# Main.net
KiCad netlist of a schematic drawn in Altium Designer
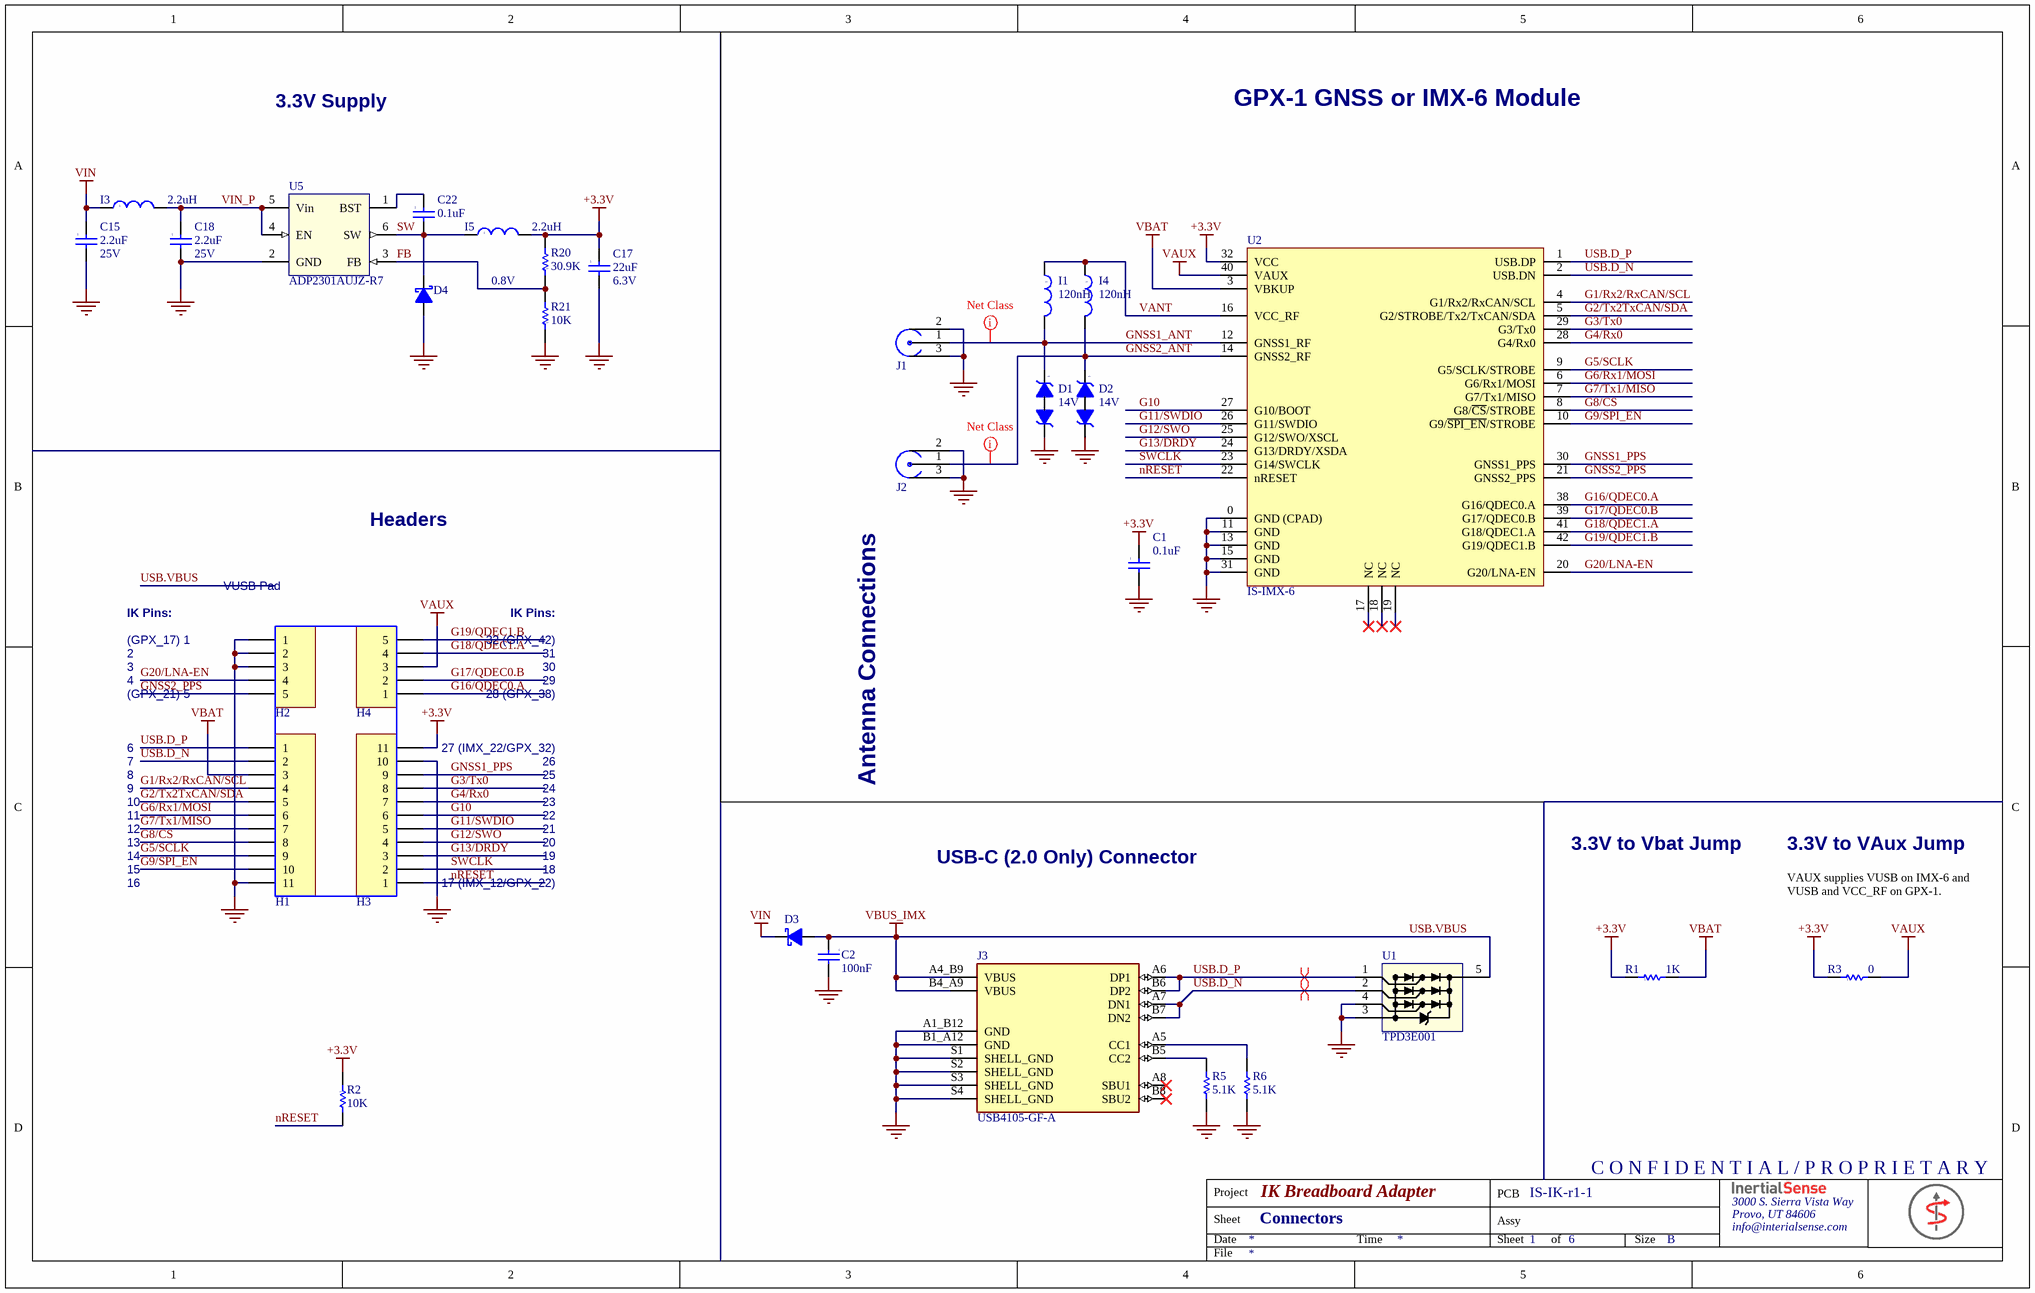
[diagram p0: Main.SchDoc]

(export (version "E")
  (design (tool "Eeschema 10.0.6"))
  (components
    (comp (ref "C1")
      (value "0.1uF")
      (footprint "0402")
      (description "CAP CER .10UF 50V X7R 10% 0402")
      (fields
        (field (name "MANUFACTURER") "TDK Corporation")
        (field (name "MANUFACTURER PART NUMBER") "C1005X7R1H104K")
        (field (name "PUBLISHER") "Altium Limited")
      )
      (libsource (lib "General") (part "Cap"))
    )
    (comp (ref "C2")
      (value "100nF")
      (footprint "0402")
      (description "CAP CER .10UF 50V X7R 10% 0402")
      (fields
        (field (name "MANUFACTURER") "TDK Corporation")
        (field (name "MANUFACTURER PART NUMBER") "C1005X7R1H104K")
        (field (name "PUBLISHER") "Altium Limited")
      )
      (libsource (lib "General") (part "Cap"))
    )
    (comp (ref "C15")
      (value "2.2uF")
      (footprint "0603")
      (description "CAP CER 2.2UF 25V X6S 0603")
      (fields
        (field (name "MANUFACTURER") "Murata")
        (field (name "MANUFACTURER PART NUMBER") "GRT188C81E225KE13D")
        (field (name "VOLTAGE RATING") "25V")
        (field (name "PUBLISHER") "Altium Limited")
      )
      (libsource (lib "General") (part "Cap"))
    )
    (comp (ref "C17")
      (value "22uF")
      (footprint "0603")
      (description "CAP CER 22UF 6.3V X6S 0603")
      (fields
        (field (name "MANUFACTURER") "Murata")
        (field (name "MANUFACTURER PART NUMBER") "GRM188C80J226ME15D")
        (field (name "VOLTAGE RATING") "6.3V")
        (field (name "PUBLISHER") "Altium Limited")
      )
      (libsource (lib "General") (part "Cap"))
    )
    (comp (ref "C18")
      (value "2.2uF")
      (footprint "0603")
      (description "CAP CER 2.2UF 25V X6S 0603")
      (fields
        (field (name "MANUFACTURER") "Murata")
        (field (name "MANUFACTURER PART NUMBER") "GRT188C81E225KE13D")
        (field (name "VOLTAGE RATING") "25V")
        (field (name "PUBLISHER") "Altium Limited")
      )
      (libsource (lib "General") (part "Cap"))
    )
    (comp (ref "C22")
      (value "0.1uF")
      (footprint "0402")
      (description "CAP CER 0.1UF 50V X7R 0402")
      (fields
        (field (name "MANUFACTURER") "TDK")
        (field (name "MANUFACTURER PART NUMBER") "CGA2B3X7R1H104K050BB")
        (field (name "PUBLISHER") "Altium Limited")
      )
      (libsource (lib "General") (part "Cap"))
    )
    (comp (ref "D1")
      (value "Diode - Bidirectional Zener")
      (footprint "R0402")
      (description "LITTELFUSE - PESD0402-140 - DIODE, ESD PROTECTION, 0402, FULL REEL")
      (fields
        (field (name "MANUFACTURER") "Littelfuse")
        (field (name "MANUFACTURER PART NUMBER") "PESD0402-140")
        (field (name "WORKING VOLTAGE") "14V")
      )
      (libsource (lib "General") (part "Diode - Bidirectional Zener"))
    )
    (comp (ref "D2")
      (value "Diode - Bidirectional Zener")
      (footprint "R0402")
      (description "LITTELFUSE - PESD0402-140 - DIODE, ESD PROTECTION, 0402, FULL REEL")
      (fields
        (field (name "MANUFACTURER") "Littelfuse")
        (field (name "MANUFACTURER PART NUMBER") "PESD0402-140")
        (field (name "WORKING VOLTAGE") "14V")
      )
      (libsource (lib "General") (part "Diode - Bidirectional Zener"))
    )
    (comp (ref "D3")
      (value "Diode - Schottky")
      (footprint "D0603B")
      (description "DIODE SCHOTTKY 30V 2A 0603")
      (fields
        (field (name "MANUFACTURER") "Vishay")
        (field (name "MANUFACTURER PART NUMBER") "VSKY20301608-G4-08")
      )
      (libsource (lib "General") (part "Diode - Schottky"))
    )
    (comp (ref "D4")
      (value "Diode - Schottky")
      (footprint "D0603B")
      (description "DIODE SCHOTTKY 30V 2A 0603")
      (fields
        (field (name "MANUFACTURER") "Vishay")
        (field (name "MANUFACTURER PART NUMBER") "VSKY20301608-G4-08")
      )
      (libsource (lib "General") (part "Diode - Schottky"))
    )
    (comp (ref "H1")
      (value "Hdr - 11pin")
      (footprint "Header-.1IN-1x11")
      (description "11 pin header")
      (libsource (lib "") (part "Hdr - 11pin_1"))
    )
    (comp (ref "H2")
      (value "Hdr - 5pin")
      (footprint "Header-.1IN-1x5")
      (description "5 pin header")
      (libsource (lib "IS-IG-BB") (part "Hdr - 5pin"))
    )
    (comp (ref "H3")
      (value "Hdr - 11pin")
      (footprint "Header-.1IN-1x11")
      (description "11 pin header")
      (libsource (lib "IS-IG-BB") (part "Hdr - 11pin"))
    )
    (comp (ref "H4")
      (value "Hdr - 5pin")
      (footprint "Header-.1IN-1x5")
      (description "5 pin header")
      (libsource (lib "") (part "Hdr - 5pin_1"))
    )
    (comp (ref "I1")
      (value "120nH")
      (footprint "0402")
      (description "Inductor RF Chip Wirewound 120nH 5% 100MHz 20Q-Factor 110mA 2.66Ohm DCR 0402 Paper T/R")
      (fields
        (field (name "MANUFACTURER") "Murata")
        (field (name "MANUFACTURER PART NUMBER") "LQW15ANR12J00D")
      )
      (libsource (lib "General") (part "Inductor"))
    )
    (comp (ref "I3")
      (value "2.2uH")
      (footprint "0806")
      (description "FIXED IND 2.2UH 1.2A 110 MOHM")
      (fields
        (field (name "MANUFACTURER") "TDK")
        (field (name "MANUFACTURER PART NUMBER") "MLP2016H2R2MT0S1")
      )
      (libsource (lib "General") (part "Inductor"))
    )
    (comp (ref "I4")
      (value "120nH")
      (footprint "0402")
      (description "Inductor RF Chip Wirewound 120nH 5% 100MHz 20Q-Factor 110mA 2.66Ohm DCR 0402 Paper T/R")
      (fields
        (field (name "MANUFACTURER") "Murata")
        (field (name "MANUFACTURER PART NUMBER") "LQW15ANR12J00D")
      )
      (libsource (lib "General") (part "Inductor"))
    )
    (comp (ref "I5")
      (value "2.2uH")
      (footprint "0806")
      (description "FIXED IND 2.2UH 1.2A 110 MOHM")
      (fields
        (field (name "MANUFACTURER") "TDK")
        (field (name "MANUFACTURER PART NUMBER") "MLP2016H2R2MT0S1")
      )
      (libsource (lib "General") (part "Inductor"))
    )
    (comp (ref "J1")
      (value "RF - GND x 2")
      (footprint "RF UMC SMD")
      (description "CONN UMC RCPT STR 50 OHM SMD")
      (fields
        (field (name "MANUFACTURER") "Emerson Network Power Connectivity Johnson")
        (field (name "MANUFACTURER PART NUMBER") "128-0711-201")
      )
      (libsource (lib "Connectors") (part "RF - GND x 2"))
    )
    (comp (ref "J2")
      (value "RF - GND x 2")
      (footprint "RF UMC SMD")
      (description "CONN UMC RCPT STR 50 OHM SMD")
      (fields
        (field (name "MANUFACTURER") "Emerson Network Power Connectivity Johnson")
        (field (name "MANUFACTURER PART NUMBER") "128-0711-201")
      )
      (libsource (lib "Connectors") (part "RF - GND x 2"))
    )
    (comp (ref "J3")
      (value "USB4105-GF-A")
      (footprint "GCT_USB4105-GF-A")
      (fields (field (name "MANUFACTURER") "GCT"))
      (libsource (lib "Connectors") (part "USB4105-GF-A"))
    )
    (comp (ref "R1")
      (value "1K")
      (footprint "R0402")
      (description "1 kOhms 1/16W Chip Resistor 0402 (1005 Metric) Moisture Resistant Thick Film")
      (fields
        (field (name "MANUFACTURER") "Yageo")
        (field (name "MANUFACTURER PART NUMBER") "RC0402FR-071KL")
      )
      (libsource (lib "General") (part "Res"))
    )
    (comp (ref "R2")
      (value "10K")
      (footprint "R0402")
      (description "10 kOhms 1/16W Chip Resistor 0402 (1005 Metric) Moisture Resistant Thick Film")
      (fields
        (field (name "MANUFACTURER") "Stackpole Electronics")
        (field (name "MANUFACTURER PART NUMBER") "RMCF0402FT10K0")
      )
      (libsource (lib "General") (part "Res"))
    )
    (comp (ref "R3")
      (value "0")
      (footprint "R0402")
      (description "0 Ohms 1/16W Chip Resistor 0402 (1005 Metric) Moisture Resistant Thick Film")
      (fields
        (field (name "MANUFACTURER") "Yageo")
        (field (name "MANUFACTURER PART NUMBER") "RC0402JR-070RL")
      )
      (libsource (lib "General") (part "Res"))
    )
    (comp (ref "R5")
      (value "5.1K")
      (footprint "R0402")
      (description "Res Thick Film 1.0 x 0.5 mm 5.1K Ohm 1% 0.063W(1/16W) 100ppm/ C Molded SMD Paper T/R")
      (fields
        (field (name "MANUFACTURER") "Yageo")
        (field (name "MANUFACTURER PART NUMBER") "RC0402FR-075K1L")
      )
      (libsource (lib "General") (part "Res"))
    )
    (comp (ref "R6")
      (value "5.1K")
      (footprint "R0402")
      (description "Res Thick Film 1.0 x 0.5 mm 5.1K Ohm 1% 0.063W(1/16W) 100ppm/ C Molded SMD Paper T/R")
      (fields
        (field (name "MANUFACTURER") "Yageo")
        (field (name "MANUFACTURER PART NUMBER") "RC0402FR-075K1L")
      )
      (libsource (lib "General") (part "Res"))
    )
    (comp (ref "R20")
      (value "30.9K")
      (footprint "R0402")
      (description "RES TF 30.9K OHM 1% 1/16W 0402")
      (fields
        (field (name "MANUFACTURER") "Stackpole Electronics Inc")
        (field (name "MANUFACTURER PART NUMBER") "RMCF0402FT30K9")
      )
      (libsource (lib "General") (part "Res"))
    )
    (comp (ref "R21")
      (value "10K")
      (footprint "R0402")
      (description "RES 10.0K OHM 1/16W 1% 0402 SMD")
      (fields
        (field (name "MANUFACTURER") "Yageo")
        (field (name "MANUFACTURER PART NUMBER") "RC0402FR-0710KL")
      )
      (libsource (lib "General") (part "Res"))
    )
    (comp (ref "U1")
      (value "TPD3E001")
      (footprint "QFN50P160X160X60-6N")
      (description "TVS DIODE 5.5V SOT5")
      (fields
        (field (name "MANUFACTURER") "Texas Instruments")
        (field (name "MANUFACTURER PART NUMBER") "TPD3E001DRLR")
      )
      (libsource (lib "ICs") (part "TPD3E001"))
    )
    (comp (ref "U2")
      (value "IMX")
      (footprint "IS-GPX-1.0")
      (description "Inertial Sense IMX")
      (fields
        (field (name "MANUFACTURER") "Inertial Sense")
        (field (name "MANUFACTURER PART NUMBER") "IS-IMX-6")
      )
      (libsource (lib "IS-GPX-1") (part "IS-GPX-1.0"))
    )
    (comp (ref "U5")
      (value "ADP2301")
      (footprint "MO-178-AB")
      (description "IC BUCK ADJ 1.2A 6TSOT")
      (fields
        (field (name "MANUFACTURER") "Analog Devices Inc")
        (field (name "MANUFACTURER PART NUMBER") "ADP2301AUJZ-R7")
      )
      (libsource (lib "ICs") (part "ADP2301"))
    )
  )
  (nets
    (net (code "1") (name "+3.3V") (class "Default")
      (node (ref "C1") (pin "1") (pinfunction "1_1") (pintype "passive"))
      (node (ref "C17") (pin "1") (pinfunction "1_1") (pintype "passive"))
      (node (ref "H3") (pin "11") (pinfunction "11_11") (pintype "passive"))
      (node (ref "I5") (pin "2") (pinfunction "2_2") (pintype "passive"))
      (node (ref "R1") (pin "1") (pinfunction "1_1") (pintype "passive"))
      (node (ref "R2") (pin "1") (pinfunction "1_1") (pintype "passive"))
      (node (ref "R20") (pin "2") (pinfunction "2_2") (pintype "passive"))
      (node (ref "R3") (pin "1") (pinfunction "1_1") (pintype "passive"))
      (node (ref "U2") (pin "32") (pinfunction "VCC_32") (pintype "power_in"))
    )
    (net (code "2") (name "/FB") (class "Default")
      (node (ref "R20") (pin "1") (pinfunction "1_1") (pintype "passive"))
      (node (ref "R21") (pin "2") (pinfunction "2_2") (pintype "passive"))
      (node (ref "U5") (pin "3") (pinfunction "FB_3") (pintype "input"))
    )
    (net (code "3") (name "/G1{slash}Rx2{slash}RxCAN{slash}SCL") (class "Default")
      (node (ref "H1") (pin "4") (pinfunction "4_4") (pintype "passive"))
      (node (ref "U2") (pin "4") (pinfunction "G1/Rx2/RxCAN/SCL_4") (pintype "passive"))
    )
    (net (code "4") (name "/G2{slash}Tx2TxCAN{slash}SDA") (class "Default")
      (node (ref "H1") (pin "5") (pinfunction "5_5") (pintype "passive"))
      (node (ref "U2") (pin "5") (pinfunction "G2/STROBE/Tx2/TxCAN/SDA_5") (pintype "passive"))
    )
    (net (code "5") (name "/G3{slash}Tx0") (class "Default")
      (node (ref "H3") (pin "8") (pinfunction "8_8") (pintype "passive"))
      (node (ref "U2") (pin "29") (pinfunction "G3/Tx0_29") (pintype "passive"))
    )
    (net (code "6") (name "/G4{slash}Rx0") (class "Default")
      (node (ref "H3") (pin "7") (pinfunction "7_7") (pintype "passive"))
      (node (ref "U2") (pin "28") (pinfunction "G4/Rx0_28") (pintype "passive"))
    )
    (net (code "7") (name "/G5{slash}SCLK") (class "Default")
      (node (ref "H1") (pin "9") (pinfunction "9_9") (pintype "passive"))
      (node (ref "U2") (pin "9") (pinfunction "G5/SCLK/STROBE_9") (pintype "passive"))
    )
    (net (code "8") (name "/G6{slash}Rx1{slash}MOSI") (class "Default")
      (node (ref "H1") (pin "6") (pinfunction "6_6") (pintype "passive"))
      (node (ref "U2") (pin "6") (pinfunction "G6/Rx1/MOSI_6") (pintype "passive"))
    )
    (net (code "9") (name "/G7{slash}Tx1{slash}MISO") (class "Default")
      (node (ref "H1") (pin "7") (pinfunction "7_7") (pintype "passive"))
      (node (ref "U2") (pin "7") (pinfunction "G7/Tx1/MISO_7") (pintype "passive"))
    )
    (net (code "10") (name "/G8{slash}~{CS}") (class "Default")
      (node (ref "H1") (pin "8") (pinfunction "8_8") (pintype "passive"))
      (node (ref "U2") (pin "8") (pinfunction "G8/~{CS}/STROBE_8") (pintype "passive"))
    )
    (net (code "11") (name "/G9{slash}~{SPI_EN}") (class "Default")
      (node (ref "H1") (pin "10") (pinfunction "10_10") (pintype "passive"))
      (node (ref "U2") (pin "10") (pinfunction "G9/~{SPI_EN}/STROBE_10") (pintype "passive"))
    )
    (net (code "12") (name "/G10") (class "Default")
      (node (ref "H3") (pin "6") (pinfunction "6_6") (pintype "passive"))
      (node (ref "U2") (pin "27") (pinfunction "G10/BOOT_27") (pintype "passive"))
    )
    (net (code "13") (name "/G11{slash}SWDIO") (class "Default")
      (node (ref "H3") (pin "5") (pinfunction "5_5") (pintype "passive"))
      (node (ref "U2") (pin "26") (pinfunction "G11/SWDIO_26") (pintype "passive"))
    )
    (net (code "14") (name "/G12{slash}SWO") (class "Default")
      (node (ref "H3") (pin "4") (pinfunction "4_4") (pintype "passive"))
      (node (ref "U2") (pin "25") (pinfunction "G12/SWO/XSCL_25") (pintype "passive"))
    )
    (net (code "15") (name "/G13{slash}DRDY") (class "Default")
      (node (ref "H3") (pin "3") (pinfunction "3_3") (pintype "passive"))
      (node (ref "U2") (pin "24") (pinfunction "G13/DRDY/XSDA_24") (pintype "passive"))
    )
    (net (code "16") (name "/G16{slash}QDEC0.A") (class "Default")
      (node (ref "H4") (pin "1") (pinfunction "1_1") (pintype "passive"))
      (node (ref "U2") (pin "38") (pinfunction "G16/QDEC0.A_38") (pintype "passive"))
    )
    (net (code "17") (name "/G17{slash}QDEC0.B") (class "Default")
      (node (ref "H4") (pin "2") (pinfunction "2_2") (pintype "passive"))
      (node (ref "U2") (pin "39") (pinfunction "G17/QDEC0.B_39") (pintype "passive"))
    )
    (net (code "18") (name "/G18{slash}QDEC1.A") (class "Default")
      (node (ref "H4") (pin "4") (pinfunction "4_4") (pintype "passive"))
      (node (ref "U2") (pin "41") (pinfunction "G18/QDEC1.A_41") (pintype "passive"))
    )
    (net (code "19") (name "/G19{slash}QDEC1.B") (class "Default")
      (node (ref "H4") (pin "5") (pinfunction "5_5") (pintype "passive"))
      (node (ref "U2") (pin "42") (pinfunction "G19/QDEC1.B_42") (pintype "passive"))
    )
    (net (code "20") (name "/G20{slash}LNA-EN") (class "Default")
      (node (ref "H2") (pin "4") (pinfunction "4_4") (pintype "passive"))
      (node (ref "U2") (pin "20") (pinfunction "G20/LNA-EN_20") (pintype "passive"))
    )
    (net (code "21") (name "/GNSS1_ANT") (class "Default")
      (node (ref "D1") (pin "1") (pinfunction "1_1") (pintype "passive"))
      (node (ref "I1") (pin "2") (pinfunction "2_2") (pintype "passive"))
      (node (ref "J1") (pin "1") (pinfunction "1_1") (pintype "passive"))
      (node (ref "U2") (pin "12") (pinfunction "GNSS1_RF_12") (pintype "passive"))
    )
    (net (code "22") (name "/GNSS1_PPS") (class "Default")
      (node (ref "H3") (pin "9") (pinfunction "9_9") (pintype "passive"))
      (node (ref "U2") (pin "30") (pinfunction "GNSS1_PPS_30") (pintype "passive"))
    )
    (net (code "23") (name "/GNSS2_ANT") (class "Default")
      (node (ref "D2") (pin "1") (pinfunction "1_1") (pintype "passive"))
      (node (ref "I4") (pin "2") (pinfunction "2_2") (pintype "passive"))
      (node (ref "J2") (pin "1") (pinfunction "1_1") (pintype "passive"))
      (node (ref "U2") (pin "14") (pinfunction "GNSS2_RF_14") (pintype "passive"))
    )
    (net (code "24") (name "/GNSS2_PPS") (class "Default")
      (node (ref "H2") (pin "5") (pinfunction "5_5") (pintype "passive"))
      (node (ref "U2") (pin "21") (pinfunction "GNSS2_PPS_21") (pintype "passive"))
    )
    (net (code "25") (name "/SW") (class "Default")
      (node (ref "C22") (pin "2") (pinfunction "2_2") (pintype "passive"))
      (node (ref "D4") (pin "C") (pinfunction "C_C") (pintype "passive"))
      (node (ref "I5") (pin "1") (pinfunction "1_1") (pintype "passive"))
      (node (ref "U5") (pin "6") (pinfunction "SW_6") (pintype "output"))
    )
    (net (code "26") (name "/SWCLK") (class "Default")
      (node (ref "H3") (pin "2") (pinfunction "2_2") (pintype "passive"))
      (node (ref "U2") (pin "23") (pinfunction "G14/SWCLK_23") (pintype "passive"))
    )
    (net (code "27") (name "/USB.D_N") (class "Default")
      (node (ref "H1") (pin "2") (pinfunction "2_2") (pintype "passive"))
      (node (ref "J3") (pin "A7") (pinfunction "DN1_A7") (pintype "bidirectional"))
      (node (ref "J3") (pin "B7") (pinfunction "DN2_B7") (pintype "bidirectional"))
      (node (ref "U1") (pin "2") (pintype "passive"))
      (node (ref "U2") (pin "2") (pinfunction "USB.DN_2") (pintype "passive"))
    )
    (net (code "28") (name "/USB.D_P") (class "Default")
      (node (ref "H1") (pin "1") (pinfunction "1_1") (pintype "passive"))
      (node (ref "J3") (pin "A6") (pinfunction "DP1_A6") (pintype "bidirectional"))
      (node (ref "J3") (pin "B6") (pinfunction "DP2_B6") (pintype "bidirectional"))
      (node (ref "U1") (pin "1") (pintype "passive"))
      (node (ref "U2") (pin "1") (pinfunction "USB.DP_1") (pintype "passive"))
    )
    (net (code "29") (name "/VANT") (class "Default")
      (node (ref "I1") (pin "1") (pinfunction "1_1") (pintype "passive"))
      (node (ref "I4") (pin "1") (pinfunction "1_1") (pintype "passive"))
      (node (ref "U2") (pin "16") (pinfunction "VCC_RF_16") (pintype "power_in"))
    )
    (net (code "30") (name "/VIN_P") (class "Default")
      (node (ref "C18") (pin "1") (pinfunction "1_1") (pintype "passive"))
      (node (ref "I3") (pin "2") (pinfunction "2_2") (pintype "passive"))
      (node (ref "U5") (pin "4") (pinfunction "EN_4") (pintype "input"))
      (node (ref "U5") (pin "5") (pinfunction "Vin_5") (pintype "power_in"))
    )
    (net (code "31") (name "/nRESET") (class "Default")
      (node (ref "H3") (pin "1") (pinfunction "1_1") (pintype "passive"))
      (node (ref "R2") (pin "2") (pinfunction "2_2") (pintype "passive"))
      (node (ref "U2") (pin "22") (pinfunction "nRESET_22") (pintype "passive"))
    )
    (net (code "32") (name "GND") (class "Default")
      (node (ref "C1") (pin "2") (pinfunction "2_2") (pintype "passive"))
      (node (ref "C15") (pin "2") (pinfunction "2_2") (pintype "passive"))
      (node (ref "C17") (pin "2") (pinfunction "2_2") (pintype "passive"))
      (node (ref "C18") (pin "2") (pinfunction "2_2") (pintype "passive"))
      (node (ref "C2") (pin "2") (pinfunction "2_2") (pintype "passive"))
      (node (ref "D1") (pin "2") (pinfunction "2_2") (pintype "passive"))
      (node (ref "D2") (pin "2") (pinfunction "2_2") (pintype "passive"))
      (node (ref "D4") (pin "A") (pinfunction "A_A") (pintype "passive"))
      (node (ref "H1") (pin "11") (pinfunction "11_11") (pintype "passive"))
      (node (ref "H2") (pin "1") (pinfunction "1_1") (pintype "passive"))
      (node (ref "H2") (pin "2") (pinfunction "2_2") (pintype "passive"))
      (node (ref "H2") (pin "3") (pinfunction "3_3") (pintype "passive"))
      (node (ref "H3") (pin "10") (pinfunction "10_10") (pintype "passive"))
      (node (ref "J1") (pin "2") (pinfunction "2_2") (pintype "passive"))
      (node (ref "J1") (pin "3") (pinfunction "3_3") (pintype "passive"))
      (node (ref "J2") (pin "2") (pinfunction "2_2") (pintype "passive"))
      (node (ref "J2") (pin "3") (pinfunction "3_3") (pintype "passive"))
      (node (ref "J3") (pin "A1_B12") (pinfunction "GND_A1_B12") (pintype "power_in"))
      (node (ref "J3") (pin "B1_A12") (pinfunction "GND_B1_A12") (pintype "power_in"))
      (node (ref "J3") (pin "S1") (pinfunction "SHELL_GND_S1") (pintype "power_in"))
      (node (ref "J3") (pin "S2") (pinfunction "SHELL_GND_S2") (pintype "power_in"))
      (node (ref "J3") (pin "S3") (pinfunction "SHELL_GND_S3") (pintype "power_in"))
      (node (ref "J3") (pin "S4") (pinfunction "SHELL_GND_S4") (pintype "power_in"))
      (node (ref "R21") (pin "1") (pinfunction "1_1") (pintype "passive"))
      (node (ref "R5") (pin "1") (pinfunction "1_1") (pintype "passive"))
      (node (ref "R6") (pin "1") (pinfunction "1_1") (pintype "passive"))
      (node (ref "U1") (pin "3") (pintype "passive"))
      (node (ref "U1") (pin "4") (pinfunction "nc_4") (pintype "passive"))
      (node (ref "U2") (pin "0") (pinfunction "GND_(CPAD)_0") (pintype "power_in"))
      (node (ref "U2") (pin "11") (pinfunction "GND_11") (pintype "power_in"))
      (node (ref "U2") (pin "13") (pinfunction "GND_13") (pintype "power_in"))
      (node (ref "U2") (pin "15") (pinfunction "GND_15") (pintype "power_in"))
      (node (ref "U2") (pin "31") (pinfunction "GND_31") (pintype "power_in"))
      (node (ref "U5") (pin "2") (pinfunction "GND_2") (pintype "power_in"))
    )
    (net (code "33") (name "Net-(J3-CC1)") (class "Default")
      (node (ref "J3") (pin "A5") (pinfunction "CC1_A5") (pintype "bidirectional"))
      (node (ref "R6") (pin "2") (pinfunction "2_2") (pintype "passive"))
    )
    (net (code "34") (name "Net-(J3-CC2)") (class "Default")
      (node (ref "J3") (pin "B5") (pinfunction "CC2_B5") (pintype "bidirectional"))
      (node (ref "R5") (pin "2") (pinfunction "2_2") (pintype "passive"))
    )
    (net (code "35") (name "Net-(U5-BST)") (class "Default")
      (node (ref "C22") (pin "1") (pinfunction "1_1") (pintype "passive"))
      (node (ref "U5") (pin "1") (pinfunction "BST_1") (pintype "passive"))
    )
    (net (code "36") (name "VAUX") (class "Default")
      (node (ref "H4") (pin "3") (pinfunction "3_3") (pintype "passive"))
      (node (ref "R3") (pin "2") (pinfunction "2_2") (pintype "passive"))
      (node (ref "U2") (pin "40") (pinfunction "VAUX_40") (pintype "power_in"))
    )
    (net (code "37") (name "VBAT") (class "Default")
      (node (ref "H1") (pin "3") (pinfunction "3_3") (pintype "passive"))
      (node (ref "R1") (pin "2") (pinfunction "2_2") (pintype "passive"))
      (node (ref "U2") (pin "3") (pinfunction "VBKUP_3") (pintype "passive"))
    )
    (net (code "38") (name "VBUS_IMX") (class "Default")
      (node (ref "C2") (pin "1") (pinfunction "1_1") (pintype "passive"))
      (node (ref "D3") (pin "A") (pinfunction "A_A") (pintype "passive"))
      (node (ref "J3") (pin "A4_B9") (pinfunction "VBUS_A4_B9") (pintype "passive"))
      (node (ref "J3") (pin "B4_A9") (pinfunction "VBUS_B4_A9") (pintype "passive"))
      (node (ref "U1") (pin "5") (pinfunction "nc_5") (pintype "passive"))
    )
    (net (code "39") (name "VIN") (class "Default")
      (node (ref "C15") (pin "1") (pinfunction "1_1") (pintype "passive"))
      (node (ref "D3") (pin "C") (pinfunction "C_C") (pintype "passive"))
      (node (ref "I3") (pin "1") (pinfunction "1_1") (pintype "passive"))
    )
    (net (code "40") (name "unconnected-(J3-SBU1-PadA8)") (class "Default")
      (node (ref "J3") (pin "A8") (pinfunction "SBU1_A8") (pintype "bidirectional+no_connect"))
    )
    (net (code "41") (name "unconnected-(J3-SBU2-PadB8)") (class "Default")
      (node (ref "J3") (pin "B8") (pinfunction "SBU2_B8") (pintype "bidirectional+no_connect"))
    )
    (net (code "42") (name "unconnected-(U2-NC-Pad17)") (class "Default")
      (node (ref "U2") (pin "17") (pinfunction "NC_17") (pintype "passive+no_connect"))
    )
    (net (code "43") (name "unconnected-(U2-NC-Pad18)") (class "Default")
      (node (ref "U2") (pin "18") (pinfunction "NC_18") (pintype "passive+no_connect"))
    )
    (net (code "44") (name "unconnected-(U2-NC-Pad19)") (class "Default")
      (node (ref "U2") (pin "19") (pinfunction "NC_19") (pintype "passive+no_connect"))
    )
  )
)
